# epic_multi_prog_a.net
KiCad netlist of a schematic drawn in EAGLE
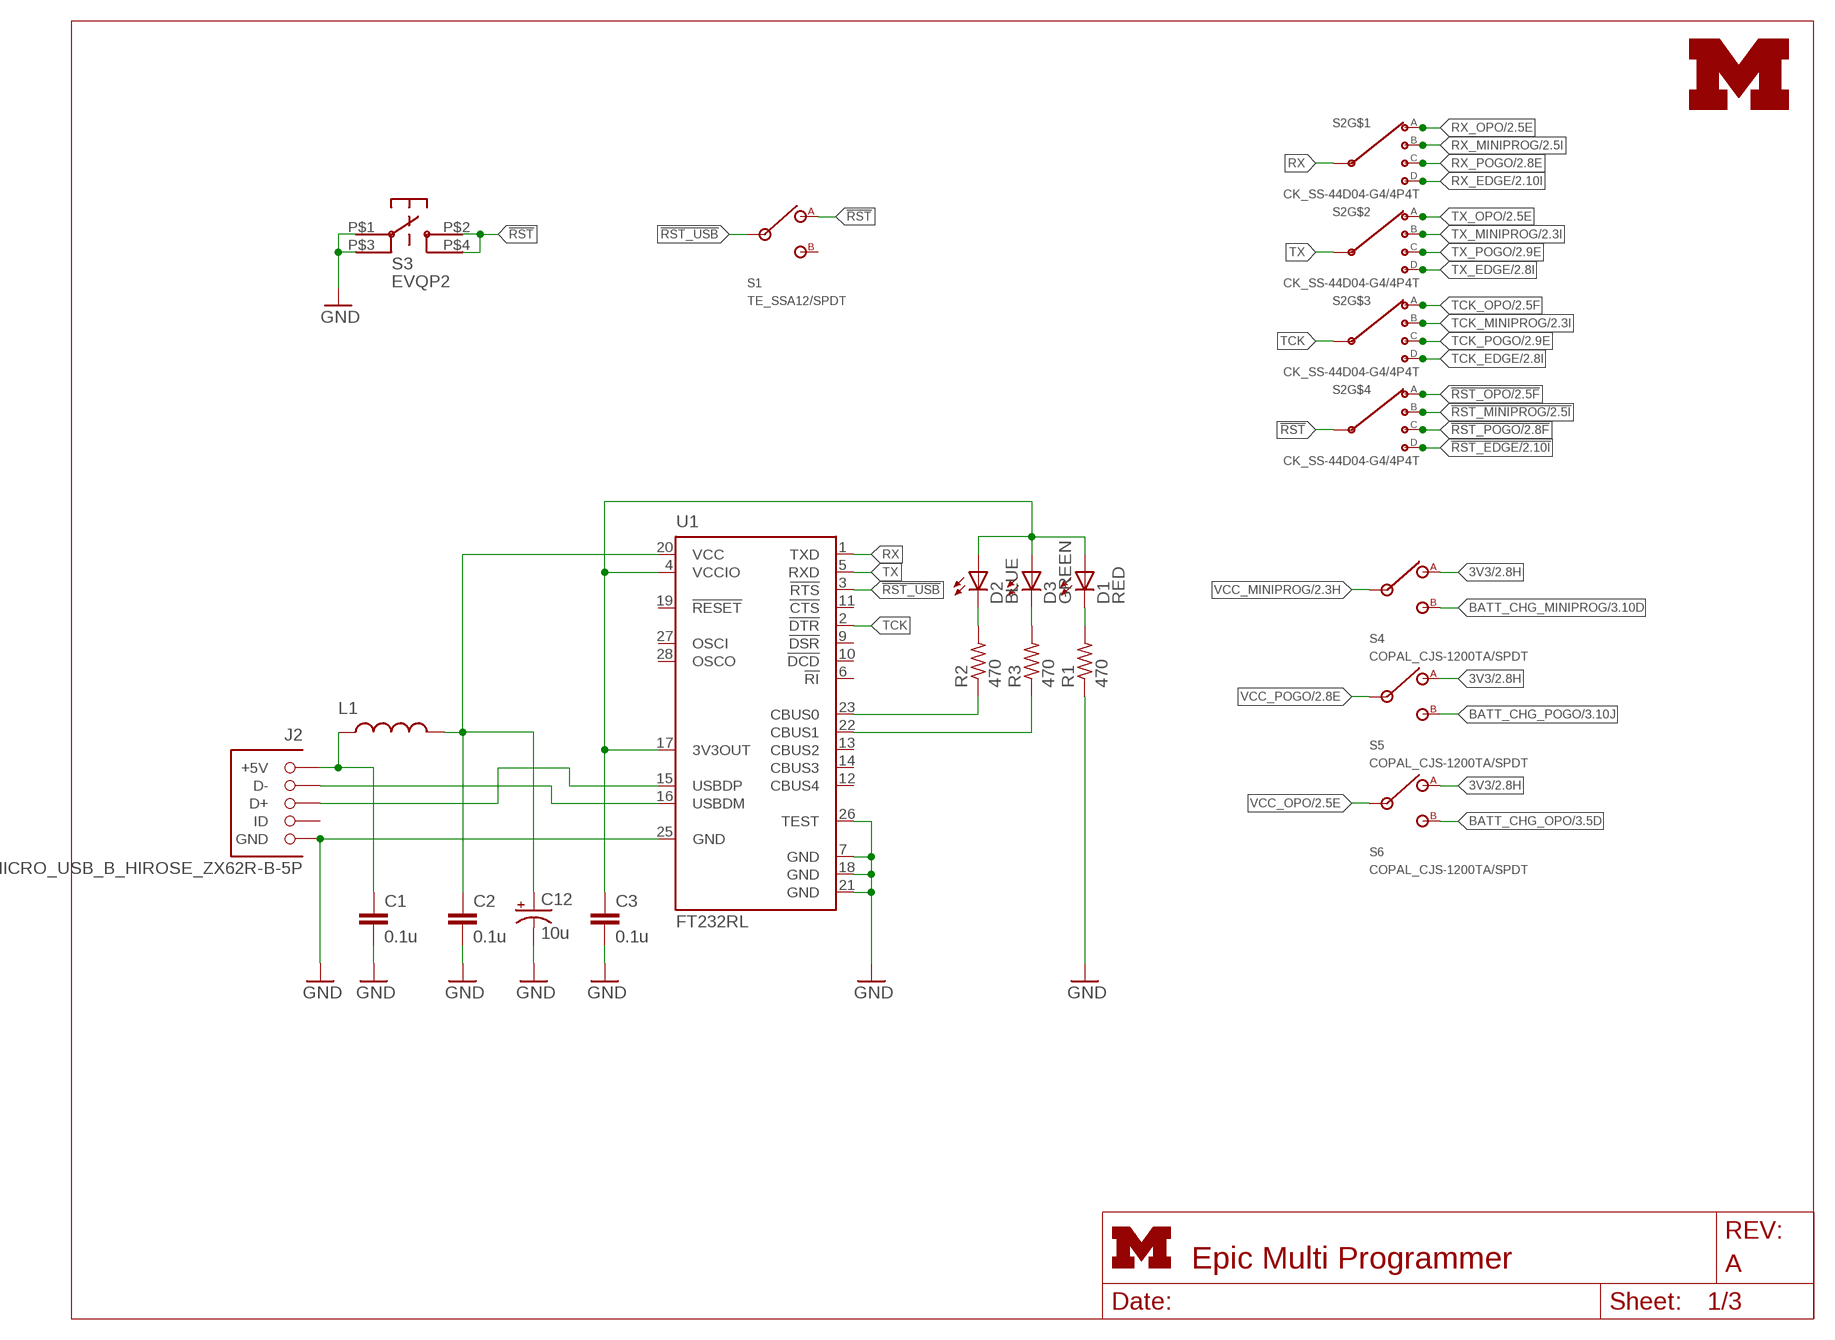
[diagram p0: schematic, sheet 1]
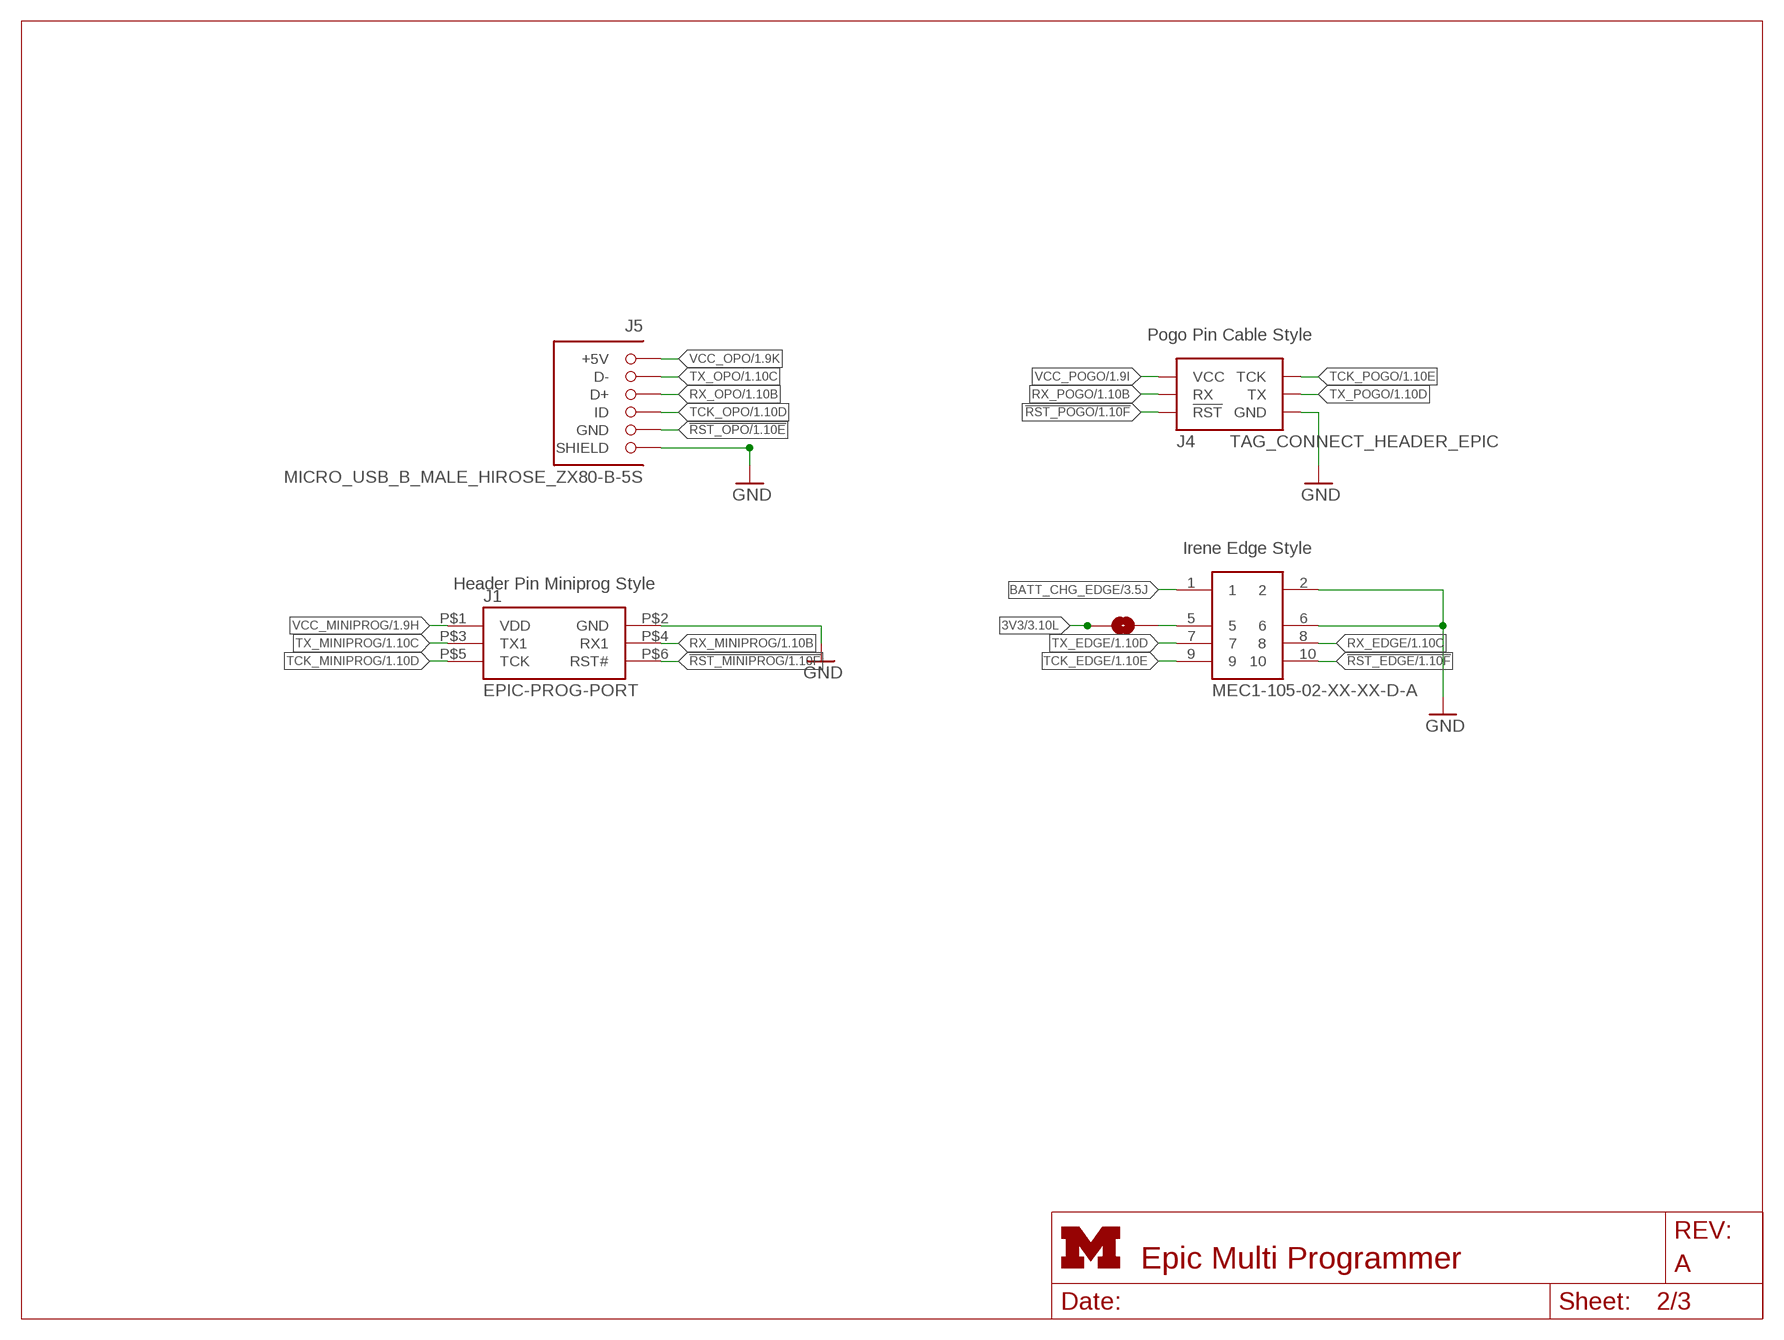
[diagram p1: schematic, sheet 2]
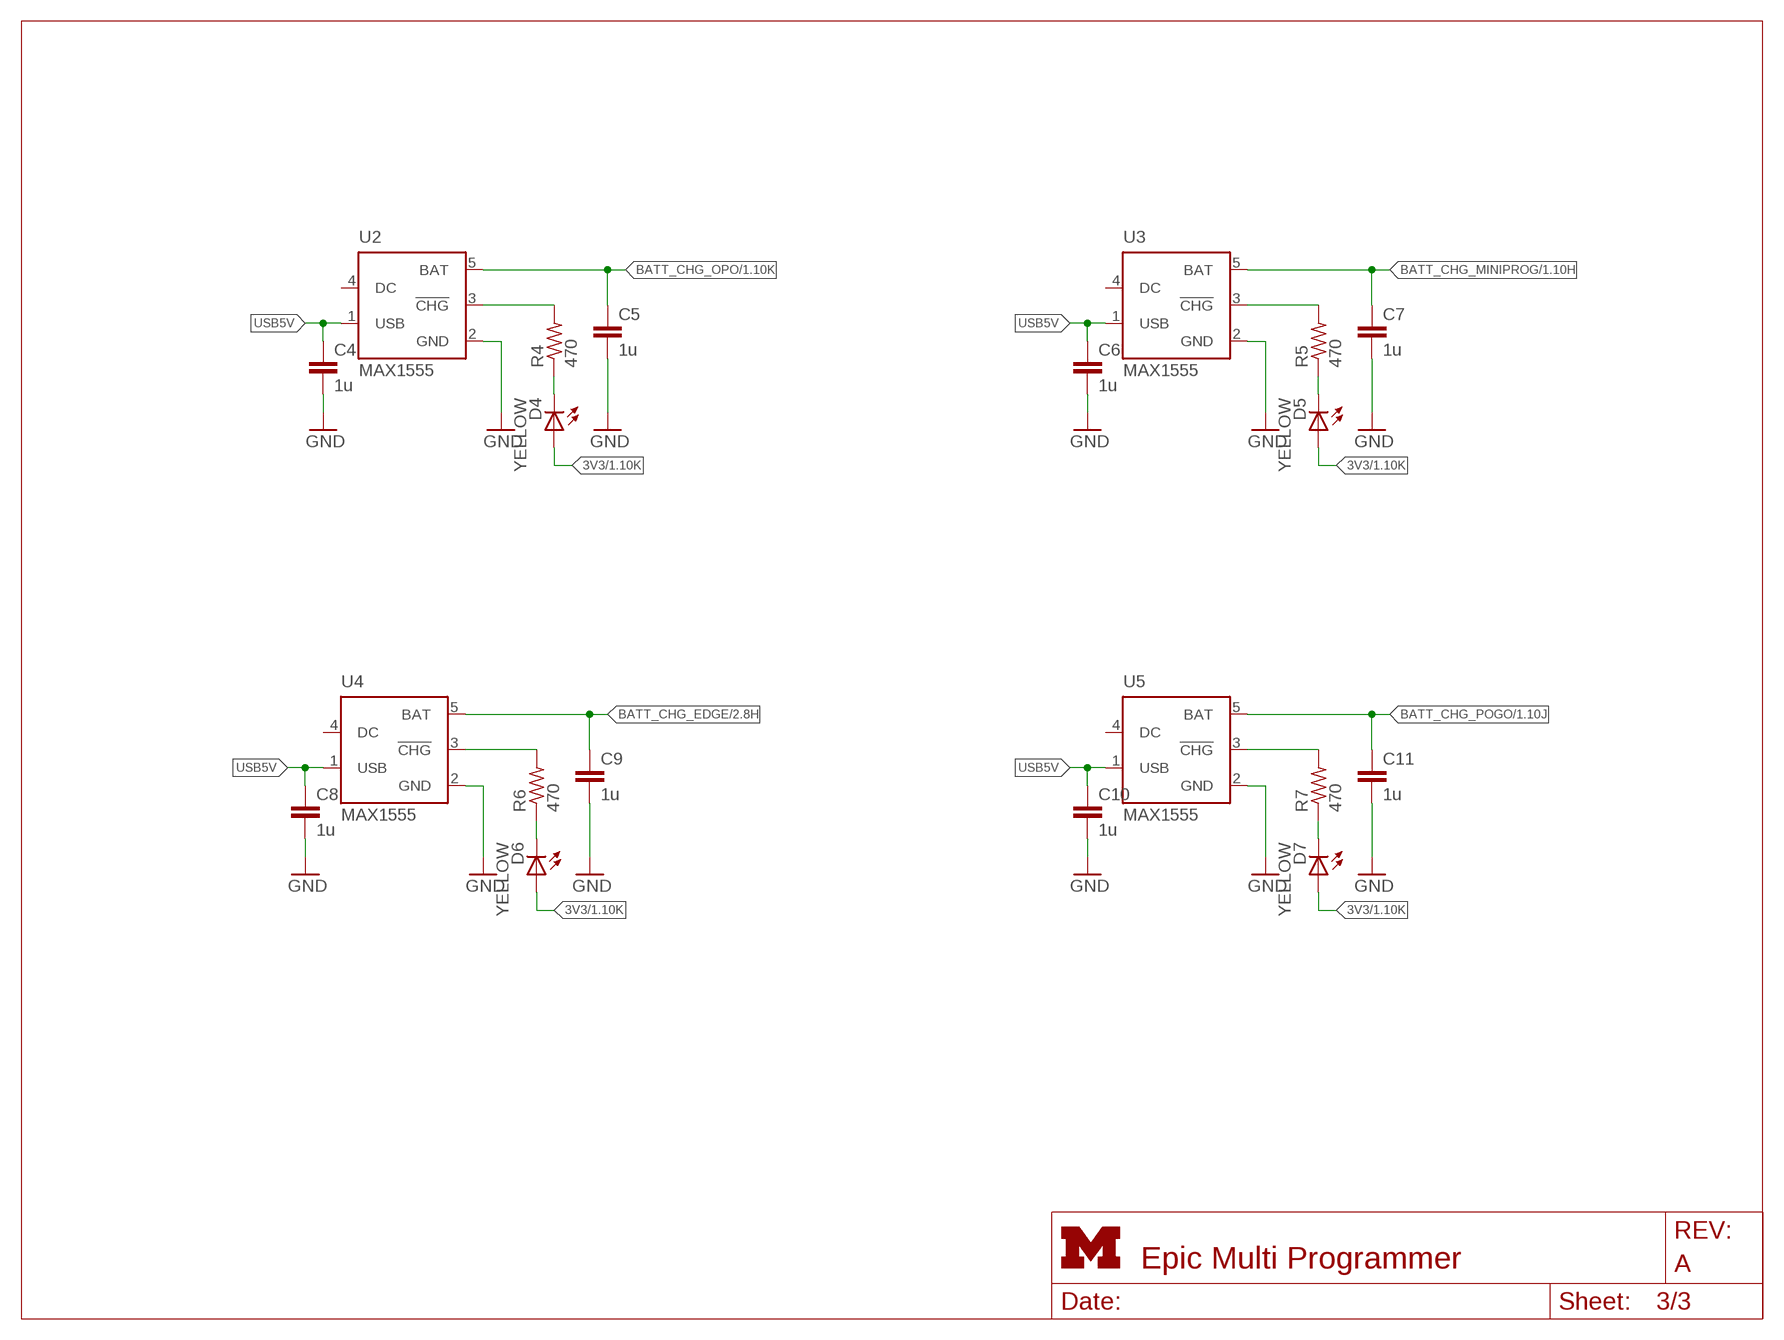
[diagram p2: schematic, sheet 3]

(export (version "E")
  (design (tool "Eeschema 10.0.6"))
  (components
    (comp (ref "C4")
      (value "1u")
      (footprint "eagle-import:C0603")
      (libsource (lib "eagle-import") (part "C-EUC0603"))
    )
    (comp (ref "C5")
      (value "1u")
      (footprint "eagle-import:C0603")
      (libsource (lib "eagle-import") (part "C-EUC0603"))
    )
    (comp (ref "C6")
      (value "1u")
      (footprint "eagle-import:C0603")
      (libsource (lib "eagle-import") (part "C-EUC0603"))
    )
    (comp (ref "C7")
      (value "1u")
      (footprint "eagle-import:C0603")
      (libsource (lib "eagle-import") (part "C-EUC0603"))
    )
    (comp (ref "C8")
      (value "1u")
      (footprint "eagle-import:C0603")
      (libsource (lib "eagle-import") (part "C-EUC0603"))
    )
    (comp (ref "C9")
      (value "1u")
      (footprint "eagle-import:C0603")
      (libsource (lib "eagle-import") (part "C-EUC0603"))
    )
    (comp (ref "C10")
      (value "1u")
      (footprint "eagle-import:C0603")
      (libsource (lib "eagle-import") (part "C-EUC0603"))
    )
    (comp (ref "C11")
      (value "1u")
      (footprint "eagle-import:C0603")
      (libsource (lib "eagle-import") (part "C-EUC0603"))
    )
    (comp (ref "D4")
      (value "YELLOW")
      (footprint "eagle-import:LED-0603")
      (libsource (lib "eagle-import") (part "LED0603"))
    )
    (comp (ref "D5")
      (value "YELLOW")
      (footprint "eagle-import:LED-0603")
      (libsource (lib "eagle-import") (part "LED0603"))
    )
    (comp (ref "D6")
      (value "YELLOW")
      (footprint "eagle-import:LED-0603")
      (libsource (lib "eagle-import") (part "LED0603"))
    )
    (comp (ref "D7")
      (value "YELLOW")
      (footprint "eagle-import:LED-0603")
      (libsource (lib "eagle-import") (part "LED0603"))
    )
    (comp (ref "R4")
      (value "470")
      (footprint "eagle-import:R0603")
      (libsource (lib "eagle-import") (part "R-US_R0603"))
    )
    (comp (ref "R5")
      (value "470")
      (footprint "eagle-import:R0603")
      (libsource (lib "eagle-import") (part "R-US_R0603"))
    )
    (comp (ref "R6")
      (value "470")
      (footprint "eagle-import:R0603")
      (libsource (lib "eagle-import") (part "R-US_R0603"))
    )
    (comp (ref "R7")
      (value "470")
      (footprint "eagle-import:R0603")
      (libsource (lib "eagle-import") (part "R-US_R0603"))
    )
    (comp (ref "U2")
      (value "MAX1555")
      (footprint "eagle-import:SOT23-5L")
      (fields (field (name "MF") "MAXIM") (field (name "MPN") "MAX1555EZK+T"))
      (libsource (lib "eagle-import") (part "MAX1555"))
    )
    (comp (ref "U3")
      (value "MAX1555")
      (footprint "eagle-import:SOT23-5L")
      (fields (field (name "MF") "MAXIM") (field (name "MPN") "MAX1555EZK+T"))
      (libsource (lib "eagle-import") (part "MAX1555"))
    )
    (comp (ref "U4")
      (value "MAX1555")
      (footprint "eagle-import:SOT23-5L")
      (fields (field (name "MF") "MAXIM") (field (name "MPN") "MAX1555EZK+T"))
      (libsource (lib "eagle-import") (part "MAX1555"))
    )
    (comp (ref "U5")
      (value "MAX1555")
      (footprint "eagle-import:SOT23-5L")
      (fields (field (name "MF") "MAXIM") (field (name "MPN") "MAX1555EZK+T"))
      (libsource (lib "eagle-import") (part "MAX1555"))
    )
    (comp (ref "J1")
      (value "EPIC-PROG-PORT")
      (footprint "eagle-import:HEADER2X3X2MM")
      (libsource (lib "eagle-import") (part "EPIC-PROG-PORT"))
    )
    (comp (ref "J3")
      (value "MEC1-105-02-XX-XX-D-A")
      (footprint "eagle-import:MEC1-105-02-XX-XX-D-A")
      (libsource (lib "eagle-import") (part "MEC1-105-02-XX-XX-D-A"))
    )
    (comp (ref "J4")
      (value "TAG_CONNECT_HEADER_EPIC")
      (footprint "eagle-import:2X3_MALE_SHROUDED_0.100")
      (libsource (lib "eagle-import") (part "TAG_CONNECT_HEADER_EPIC"))
    )
    (comp (ref "J5")
      (value "MICRO_USB_B_MALE_HIROSE_ZX80-B-5S")
      (footprint "eagle-import:USB_MICRO_B_MALE-HIROSE-ZX80-B-5S")
      (libsource (lib "eagle-import") (part "MICRO_USB_B_MALE_HIROSE_ZX80-B-5S"))
    )
    (comp (ref "SJ1")
      (value "SOLDERJUMPERNO")
      (footprint "eagle-import:SJ_2S-NO")
      (libsource (lib "eagle-import") (part "SOLDERJUMPERNO"))
    )
    (comp (ref "C1")
      (value "0.1u")
      (footprint "eagle-import:C0603")
      (libsource (lib "eagle-import") (part "C-EUC0603"))
    )
    (comp (ref "C2")
      (value "0.1u")
      (footprint "eagle-import:C0603")
      (libsource (lib "eagle-import") (part "C-EUC0603"))
    )
    (comp (ref "C3")
      (value "0.1u")
      (footprint "eagle-import:C0603")
      (libsource (lib "eagle-import") (part "C-EUC0603"))
    )
    (comp (ref "C12")
      (value "10u")
      (footprint "eagle-import:EIA3216")
      (libsource (lib "eagle-import") (part "CAP_POL1206"))
    )
    (comp (ref "D1")
      (value "RED")
      (footprint "eagle-import:LED-0603")
      (libsource (lib "eagle-import") (part "LED0603"))
    )
    (comp (ref "D2")
      (value "BLUE")
      (footprint "eagle-import:LED-0603")
      (libsource (lib "eagle-import") (part "LED0603"))
    )
    (comp (ref "D3")
      (value "GREEN")
      (footprint "eagle-import:LED-0603")
      (libsource (lib "eagle-import") (part "LED0603"))
    )
    (comp (ref "J2")
      (value "MICRO_USB_B_HIROSE_ZX62R-B-5P")
      (footprint "eagle-import:USB_MICRO_B-HIROSE-ZX62R-B-5P")
      (libsource (lib "eagle-import") (part "MICRO_USB_B_HIROSE_ZX62R-B-5P"))
    )
    (comp (ref "L1")
      (value "INDUCTOR0603")
      (footprint "eagle-import:0603")
      (libsource (lib "eagle-import") (part "INDUCTOR0603"))
    )
    (comp (ref "R1")
      (value "470")
      (footprint "eagle-import:R0603")
      (libsource (lib "eagle-import") (part "R-US_R0603"))
    )
    (comp (ref "R2")
      (value "470")
      (footprint "eagle-import:R0603")
      (libsource (lib "eagle-import") (part "R-US_R0603"))
    )
    (comp (ref "R3")
      (value "470")
      (footprint "eagle-import:R0603")
      (libsource (lib "eagle-import") (part "R-US_R0603"))
    )
    (comp (ref "S1")
      (value "TE_SSA12/SPDT")
      (footprint "eagle-import:TE_SSA12_SPDT")
      (libsource (lib "eagle-import") (part "TE_SSA12/SPDT"))
    )
    (comp (ref "S2")
      (value "CK_SS-44D04-G4/4P4T")
      (footprint "eagle-import:CK_SS-44D04-G4_4P4T")
      (fields (field (name "DIGIKEY") "CKN10389-ND"))
      (libsource (lib "eagle-import") (part "CK_SS-44D04-G4/4P4T"))
    )
    (comp (ref "S3")
      (value "EVQP2")
      (footprint "eagle-import:EVQP2")
      (libsource (lib "eagle-import") (part "EVQP2"))
    )
    (comp (ref "S4")
      (value "COPAL_CJS-1200TA/SPDT")
      (footprint "eagle-import:COPAL_CJS-1200TA_SPDT")
      (libsource (lib "eagle-import") (part "COPAL_CJS-1200TA/SPDT"))
    )
    (comp (ref "S5")
      (value "COPAL_CJS-1200TA/SPDT")
      (footprint "eagle-import:COPAL_CJS-1200TA_SPDT")
      (libsource (lib "eagle-import") (part "COPAL_CJS-1200TA/SPDT"))
    )
    (comp (ref "S6")
      (value "COPAL_CJS-1200TA/SPDT")
      (footprint "eagle-import:COPAL_CJS-1200TA_SPDT")
      (libsource (lib "eagle-import") (part "COPAL_CJS-1200TA/SPDT"))
    )
    (comp (ref "U$1")
      (value "UMICH_SOLID_SMALL")
      (footprint "eagle-import:UMICH_SOLID_75MIL")
      (libsource (lib "eagle-import") (part "UMICH_SOLID_SMALL"))
    )
    (comp (ref "U1")
      (value "FT232RL")
      (footprint "eagle-import:SSOP28")
      (libsource (lib "eagle-import") (part "FT232RL"))
    )
  )
  (nets
    (net (code "1") (name "3V3") (class "Default")
      (node (ref "C3") (pin "1") (pinfunction "1_1") (pintype "passive"))
      (node (ref "D1") (pin "A") (pinfunction "A_A") (pintype "passive"))
      (node (ref "D2") (pin "A") (pinfunction "A_A") (pintype "passive"))
      (node (ref "D3") (pin "A") (pinfunction "A_A") (pintype "passive"))
      (node (ref "D4") (pin "A") (pinfunction "A_A") (pintype "passive"))
      (node (ref "D5") (pin "A") (pinfunction "A_A") (pintype "passive"))
      (node (ref "D6") (pin "A") (pinfunction "A_A") (pintype "passive"))
      (node (ref "D7") (pin "A") (pinfunction "A_A") (pintype "passive"))
      (node (ref "S4") (pin "2") (pinfunction "A_2") (pintype "bidirectional"))
      (node (ref "S5") (pin "2") (pinfunction "A_2") (pintype "bidirectional"))
      (node (ref "S6") (pin "2") (pinfunction "A_2") (pintype "bidirectional"))
      (node (ref "SJ1") (pin "1") (pinfunction "1_1") (pintype "passive"))
      (node (ref "U1") (pin "17") (pinfunction "3V3OUT_17") (pintype "output"))
      (node (ref "U1") (pin "4") (pinfunction "VCCIO_4") (pintype "power_in"))
    )
    (net (code "2") (name "BATT_CHG_EDGE") (class "Default")
      (node (ref "C9") (pin "1") (pinfunction "1_1") (pintype "passive"))
      (node (ref "J3") (pin "1") (pinfunction "1_1") (pintype "bidirectional"))
      (node (ref "U4") (pin "5") (pinfunction "BAT_5") (pintype "passive"))
    )
    (net (code "3") (name "BATT_CHG_MINIPROG") (class "Default")
      (node (ref "C7") (pin "1") (pinfunction "1_1") (pintype "passive"))
      (node (ref "S4") (pin "1") (pinfunction "B_1") (pintype "bidirectional"))
      (node (ref "U3") (pin "5") (pinfunction "BAT_5") (pintype "passive"))
    )
    (net (code "4") (name "BATT_CHG_OPO") (class "Default")
      (node (ref "C5") (pin "1") (pinfunction "1_1") (pintype "passive"))
      (node (ref "S6") (pin "1") (pinfunction "B_1") (pintype "bidirectional"))
      (node (ref "U2") (pin "5") (pinfunction "BAT_5") (pintype "passive"))
    )
    (net (code "5") (name "BATT_CHG_POGO") (class "Default")
      (node (ref "C11") (pin "1") (pinfunction "1_1") (pintype "passive"))
      (node (ref "S5") (pin "1") (pinfunction "B_1") (pintype "bidirectional"))
      (node (ref "U5") (pin "5") (pinfunction "BAT_5") (pintype "passive"))
    )
    (net (code "6") (name "GND") (class "Default")
      (node (ref "C1") (pin "2") (pinfunction "2_2") (pintype "passive"))
      (node (ref "C10") (pin "2") (pinfunction "2_2") (pintype "passive"))
      (node (ref "C11") (pin "2") (pinfunction "2_2") (pintype "passive"))
      (node (ref "C12") (pin "C") (pinfunction "-_C") (pintype "passive"))
      (node (ref "C2") (pin "2") (pinfunction "2_2") (pintype "passive"))
      (node (ref "C3") (pin "2") (pinfunction "2_2") (pintype "passive"))
      (node (ref "C4") (pin "2") (pinfunction "2_2") (pintype "passive"))
      (node (ref "C5") (pin "2") (pinfunction "2_2") (pintype "passive"))
      (node (ref "C6") (pin "2") (pinfunction "2_2") (pintype "passive"))
      (node (ref "C7") (pin "2") (pinfunction "2_2") (pintype "passive"))
      (node (ref "C8") (pin "2") (pinfunction "2_2") (pintype "passive"))
      (node (ref "C9") (pin "2") (pinfunction "2_2") (pintype "passive"))
      (node (ref "J1") (pin "P$2") (pinfunction "GND_P$2") (pintype "bidirectional"))
      (node (ref "J2") (pin "5") (pinfunction "GND_5") (pintype "bidirectional"))
      (node (ref "J3") (pin "2") (pinfunction "2_2") (pintype "bidirectional"))
      (node (ref "J3") (pin "6") (pinfunction "6_6") (pintype "bidirectional"))
      (node (ref "J4") (pin "2") (pinfunction "GND_2") (pintype "bidirectional"))
      (node (ref "J5") (pin "SHIELD1") (pinfunction "SHIELD_SHIELD1") (pintype "bidirectional"))
      (node (ref "J5") (pin "SHIELD2") (pinfunction "SHIELD_SHIELD2") (pintype "bidirectional"))
      (node (ref "J5") (pin "SHIELD3") (pinfunction "SHIELD_SHIELD3") (pintype "bidirectional"))
      (node (ref "J5") (pin "SHIELD4") (pinfunction "SHIELD_SHIELD4") (pintype "bidirectional"))
      (node (ref "R1") (pin "1") (pinfunction "1_1") (pintype "passive"))
      (node (ref "S3") (pin "P$1") (pinfunction "P$1_P$1") (pintype "passive"))
      (node (ref "S3") (pin "P$3") (pinfunction "P$3_P$3") (pintype "passive"))
      (node (ref "U1") (pin "18") (pinfunction "GND_18") (pintype "power_in"))
      (node (ref "U1") (pin "21") (pinfunction "GND_21") (pintype "power_in"))
      (node (ref "U1") (pin "25") (pinfunction "GND_25") (pintype "power_in"))
      (node (ref "U1") (pin "26") (pinfunction "TEST_26") (pintype "input"))
      (node (ref "U1") (pin "7") (pinfunction "GND_7") (pintype "power_in"))
      (node (ref "U2") (pin "2") (pinfunction "GND_2") (pintype "power_in"))
      (node (ref "U3") (pin "2") (pinfunction "GND_2") (pintype "power_in"))
      (node (ref "U4") (pin "2") (pinfunction "GND_2") (pintype "power_in"))
      (node (ref "U5") (pin "2") (pinfunction "GND_2") (pintype "power_in"))
    )
    (net (code "7") (name "Net-(C12-+)") (class "Default")
      (node (ref "C12") (pin "A") (pinfunction "+_A") (pintype "passive"))
      (node (ref "C2") (pin "1") (pinfunction "1_1") (pintype "passive"))
      (node (ref "L1") (pin "2") (pinfunction "2_2") (pintype "passive"))
      (node (ref "U1") (pin "20") (pinfunction "VCC_20") (pintype "power_in"))
    )
    (net (code "8") (name "Net-(D1-PadC)") (class "Default")
      (node (ref "D1") (pin "C") (pinfunction "C_C") (pintype "passive"))
      (node (ref "R1") (pin "2") (pinfunction "2_2") (pintype "passive"))
    )
    (net (code "9") (name "Net-(D2-PadC)") (class "Default")
      (node (ref "D2") (pin "C") (pinfunction "C_C") (pintype "passive"))
      (node (ref "R2") (pin "2") (pinfunction "2_2") (pintype "passive"))
    )
    (net (code "10") (name "Net-(D3-PadC)") (class "Default")
      (node (ref "D3") (pin "C") (pinfunction "C_C") (pintype "passive"))
      (node (ref "R3") (pin "2") (pinfunction "2_2") (pintype "passive"))
    )
    (net (code "11") (name "Net-(D4-PadC)") (class "Default")
      (node (ref "D4") (pin "C") (pinfunction "C_C") (pintype "passive"))
      (node (ref "R4") (pin "1") (pinfunction "1_1") (pintype "passive"))
    )
    (net (code "12") (name "Net-(D5-PadC)") (class "Default")
      (node (ref "D5") (pin "C") (pinfunction "C_C") (pintype "passive"))
      (node (ref "R5") (pin "1") (pinfunction "1_1") (pintype "passive"))
    )
    (net (code "13") (name "Net-(D6-PadC)") (class "Default")
      (node (ref "D6") (pin "C") (pinfunction "C_C") (pintype "passive"))
      (node (ref "R6") (pin "1") (pinfunction "1_1") (pintype "passive"))
    )
    (net (code "14") (name "Net-(D7-PadC)") (class "Default")
      (node (ref "D7") (pin "C") (pinfunction "C_C") (pintype "passive"))
      (node (ref "R7") (pin "1") (pinfunction "1_1") (pintype "passive"))
    )
    (net (code "15") (name "Net-(J2-D+)") (class "Default")
      (node (ref "J2") (pin "3") (pinfunction "D+_3") (pintype "bidirectional"))
      (node (ref "U1") (pin "15") (pinfunction "USBDP_15") (pintype "bidirectional"))
    )
    (net (code "16") (name "Net-(J2-D-)") (class "Default")
      (node (ref "J2") (pin "2") (pinfunction "D-_2") (pintype "bidirectional"))
      (node (ref "U1") (pin "16") (pinfunction "USBDM_16") (pintype "bidirectional"))
    )
    (net (code "17") (name "Net-(J3-Pad5)") (class "Default")
      (node (ref "J3") (pin "5") (pinfunction "5_5") (pintype "bidirectional"))
      (node (ref "SJ1") (pin "2") (pinfunction "2_2") (pintype "passive"))
    )
    (net (code "18") (name "Net-(U1-CBUS0)") (class "Default")
      (node (ref "R2") (pin "1") (pinfunction "1_1") (pintype "passive"))
      (node (ref "U1") (pin "23") (pinfunction "CBUS0_23") (pintype "bidirectional"))
    )
    (net (code "19") (name "Net-(U1-CBUS1)") (class "Default")
      (node (ref "R3") (pin "1") (pinfunction "1_1") (pintype "passive"))
      (node (ref "U1") (pin "22") (pinfunction "CBUS1_22") (pintype "bidirectional"))
    )
    (net (code "20") (name "Net-(U2-~{CHG})") (class "Default")
      (node (ref "R4") (pin "2") (pinfunction "2_2") (pintype "passive"))
      (node (ref "U2") (pin "3") (pinfunction "~{CHG}_3") (pintype "output"))
    )
    (net (code "21") (name "Net-(U3-~{CHG})") (class "Default")
      (node (ref "R5") (pin "2") (pinfunction "2_2") (pintype "passive"))
      (node (ref "U3") (pin "3") (pinfunction "~{CHG}_3") (pintype "output"))
    )
    (net (code "22") (name "Net-(U4-~{CHG})") (class "Default")
      (node (ref "R6") (pin "2") (pinfunction "2_2") (pintype "passive"))
      (node (ref "U4") (pin "3") (pinfunction "~{CHG}_3") (pintype "output"))
    )
    (net (code "23") (name "Net-(U5-~{CHG})") (class "Default")
      (node (ref "R7") (pin "2") (pinfunction "2_2") (pintype "passive"))
      (node (ref "U5") (pin "3") (pinfunction "~{CHG}_3") (pintype "output"))
    )
    (net (code "24") (name "RX") (class "Default")
      (node (ref "S2") (pin "INA") (pinfunction "INPUT_INA") (pintype "bidirectional"))
      (node (ref "U1") (pin "1") (pinfunction "TXD_1") (pintype "output"))
    )
    (net (code "25") (name "RX_EDGE") (class "Default")
      (node (ref "J3") (pin "8") (pinfunction "8_8") (pintype "bidirectional"))
      (node (ref "S2") (pin "A4") (pinfunction "D_A4") (pintype "bidirectional"))
    )
    (net (code "26") (name "RX_MINIPROG") (class "Default")
      (node (ref "J1") (pin "P$4") (pinfunction "RX1_P$4") (pintype "bidirectional"))
      (node (ref "S2") (pin "A2") (pinfunction "B_A2") (pintype "bidirectional"))
    )
    (net (code "27") (name "RX_OPO") (class "Default")
      (node (ref "J5") (pin "3") (pinfunction "D+_3") (pintype "bidirectional"))
      (node (ref "S2") (pin "A1") (pinfunction "A_A1") (pintype "bidirectional"))
    )
    (net (code "28") (name "RX_POGO") (class "Default")
      (node (ref "J4") (pin "4") (pinfunction "RX_4") (pintype "bidirectional"))
      (node (ref "S2") (pin "A3") (pinfunction "C_A3") (pintype "bidirectional"))
    )
    (net (code "29") (name "TCK") (class "Default")
      (node (ref "S2") (pin "INC") (pinfunction "INPUT_INC") (pintype "bidirectional"))
      (node (ref "U1") (pin "2") (pinfunction "~{DTR}_2") (pintype "output"))
    )
    (net (code "30") (name "TCK_EDGE") (class "Default")
      (node (ref "J3") (pin "9") (pinfunction "9_9") (pintype "bidirectional"))
      (node (ref "S2") (pin "C4") (pinfunction "D_C4") (pintype "bidirectional"))
    )
    (net (code "31") (name "TCK_MINIPROG") (class "Default")
      (node (ref "J1") (pin "P$5") (pinfunction "TCK_P$5") (pintype "bidirectional"))
      (node (ref "S2") (pin "C2") (pinfunction "B_C2") (pintype "bidirectional"))
    )
    (net (code "32") (name "TCK_OPO") (class "Default")
      (node (ref "J5") (pin "4") (pinfunction "ID_4") (pintype "bidirectional"))
      (node (ref "S2") (pin "C1") (pinfunction "A_C1") (pintype "bidirectional"))
    )
    (net (code "33") (name "TCK_POGO") (class "Default")
      (node (ref "J4") (pin "5") (pinfunction "TCK_5") (pintype "bidirectional"))
      (node (ref "S2") (pin "C3") (pinfunction "C_C3") (pintype "bidirectional"))
    )
    (net (code "34") (name "TX") (class "Default")
      (node (ref "S2") (pin "INB") (pinfunction "INPUT_INB") (pintype "bidirectional"))
      (node (ref "U1") (pin "5") (pinfunction "RXD_5") (pintype "input"))
    )
    (net (code "35") (name "TX_EDGE") (class "Default")
      (node (ref "J3") (pin "7") (pinfunction "7_7") (pintype "bidirectional"))
      (node (ref "S2") (pin "B4") (pinfunction "D_B4") (pintype "bidirectional"))
    )
    (net (code "36") (name "TX_MINIPROG") (class "Default")
      (node (ref "J1") (pin "P$3") (pinfunction "TX1_P$3") (pintype "bidirectional"))
      (node (ref "S2") (pin "B2") (pinfunction "B_B2") (pintype "bidirectional"))
    )
    (net (code "37") (name "TX_OPO") (class "Default")
      (node (ref "J5") (pin "2") (pinfunction "D-_2") (pintype "bidirectional"))
      (node (ref "S2") (pin "B1") (pinfunction "A_B1") (pintype "bidirectional"))
    )
    (net (code "38") (name "TX_POGO") (class "Default")
      (node (ref "J4") (pin "3") (pinfunction "TX_3") (pintype "bidirectional"))
      (node (ref "S2") (pin "B3") (pinfunction "C_B3") (pintype "bidirectional"))
    )
    (net (code "39") (name "USB5V") (class "Default")
      (node (ref "C1") (pin "1") (pinfunction "1_1") (pintype "passive"))
      (node (ref "C10") (pin "1") (pinfunction "1_1") (pintype "passive"))
      (node (ref "C4") (pin "1") (pinfunction "1_1") (pintype "passive"))
      (node (ref "C6") (pin "1") (pinfunction "1_1") (pintype "passive"))
      (node (ref "C8") (pin "1") (pinfunction "1_1") (pintype "passive"))
      (node (ref "J2") (pin "1") (pinfunction "+5V_1") (pintype "bidirectional"))
      (node (ref "L1") (pin "1") (pinfunction "1_1") (pintype "passive"))
      (node (ref "U2") (pin "1") (pinfunction "USB_1") (pintype "input"))
      (node (ref "U3") (pin "1") (pinfunction "USB_1") (pintype "input"))
      (node (ref "U4") (pin "1") (pinfunction "USB_1") (pintype "input"))
      (node (ref "U5") (pin "1") (pinfunction "USB_1") (pintype "input"))
    )
    (net (code "40") (name "VCC_MINIPROG") (class "Default")
      (node (ref "J1") (pin "P$1") (pinfunction "VDD_P$1") (pintype "bidirectional"))
      (node (ref "S4") (pin "IN") (pinfunction "IN_IN") (pintype "bidirectional"))
    )
    (net (code "41") (name "VCC_OPO") (class "Default")
      (node (ref "J5") (pin "1") (pinfunction "+5V_1") (pintype "bidirectional"))
      (node (ref "S6") (pin "IN") (pinfunction "IN_IN") (pintype "bidirectional"))
    )
    (net (code "42") (name "VCC_POGO") (class "Default")
      (node (ref "J4") (pin "1") (pinfunction "VCC_1") (pintype "bidirectional"))
      (node (ref "S5") (pin "IN") (pinfunction "IN_IN") (pintype "bidirectional"))
    )
    (net (code "43") (name "unconnected-(J2-ID-Pad4)") (class "Default")
      (node (ref "J2") (pin "4") (pinfunction "ID_4") (pintype "bidirectional"))
    )
    (net (code "44") (name "unconnected-(S1-B-Pad2)") (class "Default")
      (node (ref "S1") (pin "2") (pinfunction "B_2") (pintype "bidirectional"))
    )
    (net (code "45") (name "unconnected-(U1-CBUS2-Pad13)") (class "Default")
      (node (ref "U1") (pin "13") (pinfunction "CBUS2_13") (pintype "bidirectional"))
    )
    (net (code "46") (name "unconnected-(U1-CBUS3-Pad14)") (class "Default")
      (node (ref "U1") (pin "14") (pinfunction "CBUS3_14") (pintype "bidirectional"))
    )
    (net (code "47") (name "unconnected-(U1-CBUS4-Pad12)") (class "Default")
      (node (ref "U1") (pin "12") (pinfunction "CBUS4_12") (pintype "bidirectional"))
    )
    (net (code "48") (name "unconnected-(U1-OSCI-Pad27)") (class "Default")
      (node (ref "U1") (pin "27") (pinfunction "OSCI_27") (pintype "input"))
    )
    (net (code "49") (name "unconnected-(U1-OSCO-Pad28)") (class "Default")
      (node (ref "U1") (pin "28") (pinfunction "OSCO_28") (pintype "output"))
    )
    (net (code "50") (name "unconnected-(U1-~{CTS}-Pad11)") (class "Default")
      (node (ref "U1") (pin "11") (pinfunction "~{CTS}_11") (pintype "input"))
    )
    (net (code "51") (name "unconnected-(U1-~{DCD}-Pad10)") (class "Default")
      (node (ref "U1") (pin "10") (pinfunction "~{DCD}_10") (pintype "input"))
    )
    (net (code "52") (name "unconnected-(U1-~{DSR}-Pad9)") (class "Default")
      (node (ref "U1") (pin "9") (pinfunction "~{DSR}_9") (pintype "input"))
    )
    (net (code "53") (name "unconnected-(U1-~{RESET}-Pad19)") (class "Default")
      (node (ref "U1") (pin "19") (pinfunction "~{RESET}_19") (pintype "input"))
    )
    (net (code "54") (name "unconnected-(U1-~{RI}-Pad6)") (class "Default")
      (node (ref "U1") (pin "6") (pinfunction "~{RI}_6") (pintype "input"))
    )
    (net (code "55") (name "unconnected-(U2-DC-Pad4)") (class "Default")
      (node (ref "U2") (pin "4") (pinfunction "DC_4") (pintype "input"))
    )
    (net (code "56") (name "unconnected-(U3-DC-Pad4)") (class "Default")
      (node (ref "U3") (pin "4") (pinfunction "DC_4") (pintype "input"))
    )
    (net (code "57") (name "unconnected-(U4-DC-Pad4)") (class "Default")
      (node (ref "U4") (pin "4") (pinfunction "DC_4") (pintype "input"))
    )
    (net (code "58") (name "unconnected-(U5-DC-Pad4)") (class "Default")
      (node (ref "U5") (pin "4") (pinfunction "DC_4") (pintype "input"))
    )
    (net (code "59") (name "~{RST_EDGE}") (class "Default")
      (node (ref "J3") (pin "10") (pinfunction "10_10") (pintype "bidirectional"))
      (node (ref "S2") (pin "D4") (pinfunction "D_D4") (pintype "bidirectional"))
    )
    (net (code "60") (name "~{RST_MINIPROG}") (class "Default")
      (node (ref "J1") (pin "P$6") (pinfunction "RST#_P$6") (pintype "bidirectional"))
      (node (ref "S2") (pin "D2") (pinfunction "B_D2") (pintype "bidirectional"))
    )
    (net (code "61") (name "~{RST_OPO}") (class "Default")
      (node (ref "J5") (pin "5") (pinfunction "GND_5") (pintype "bidirectional"))
      (node (ref "S2") (pin "D1") (pinfunction "A_D1") (pintype "bidirectional"))
    )
    (net (code "62") (name "~{RST_POGO}") (class "Default")
      (node (ref "J4") (pin "6") (pinfunction "~{RST}_6") (pintype "bidirectional"))
      (node (ref "S2") (pin "D3") (pinfunction "C_D3") (pintype "bidirectional"))
    )
    (net (code "63") (name "~{RST_USB}") (class "Default")
      (node (ref "S1") (pin "IN") (pinfunction "IN_IN") (pintype "bidirectional"))
      (node (ref "U1") (pin "3") (pinfunction "~{RTS}_3") (pintype "output"))
    )
    (net (code "64") (name "~{RST}") (class "Default")
      (node (ref "S1") (pin "1") (pinfunction "A_1") (pintype "bidirectional"))
      (node (ref "S2") (pin "IND") (pinfunction "INPUT_IND") (pintype "bidirectional"))
      (node (ref "S3") (pin "P$2") (pinfunction "P$2_P$2") (pintype "passive"))
      (node (ref "S3") (pin "P$4") (pinfunction "P$4_P$4") (pintype "passive"))
    )
  )
)
